# EVB_Gatedriver.net
KiCad netlist of a schematic drawn in Altium Designer
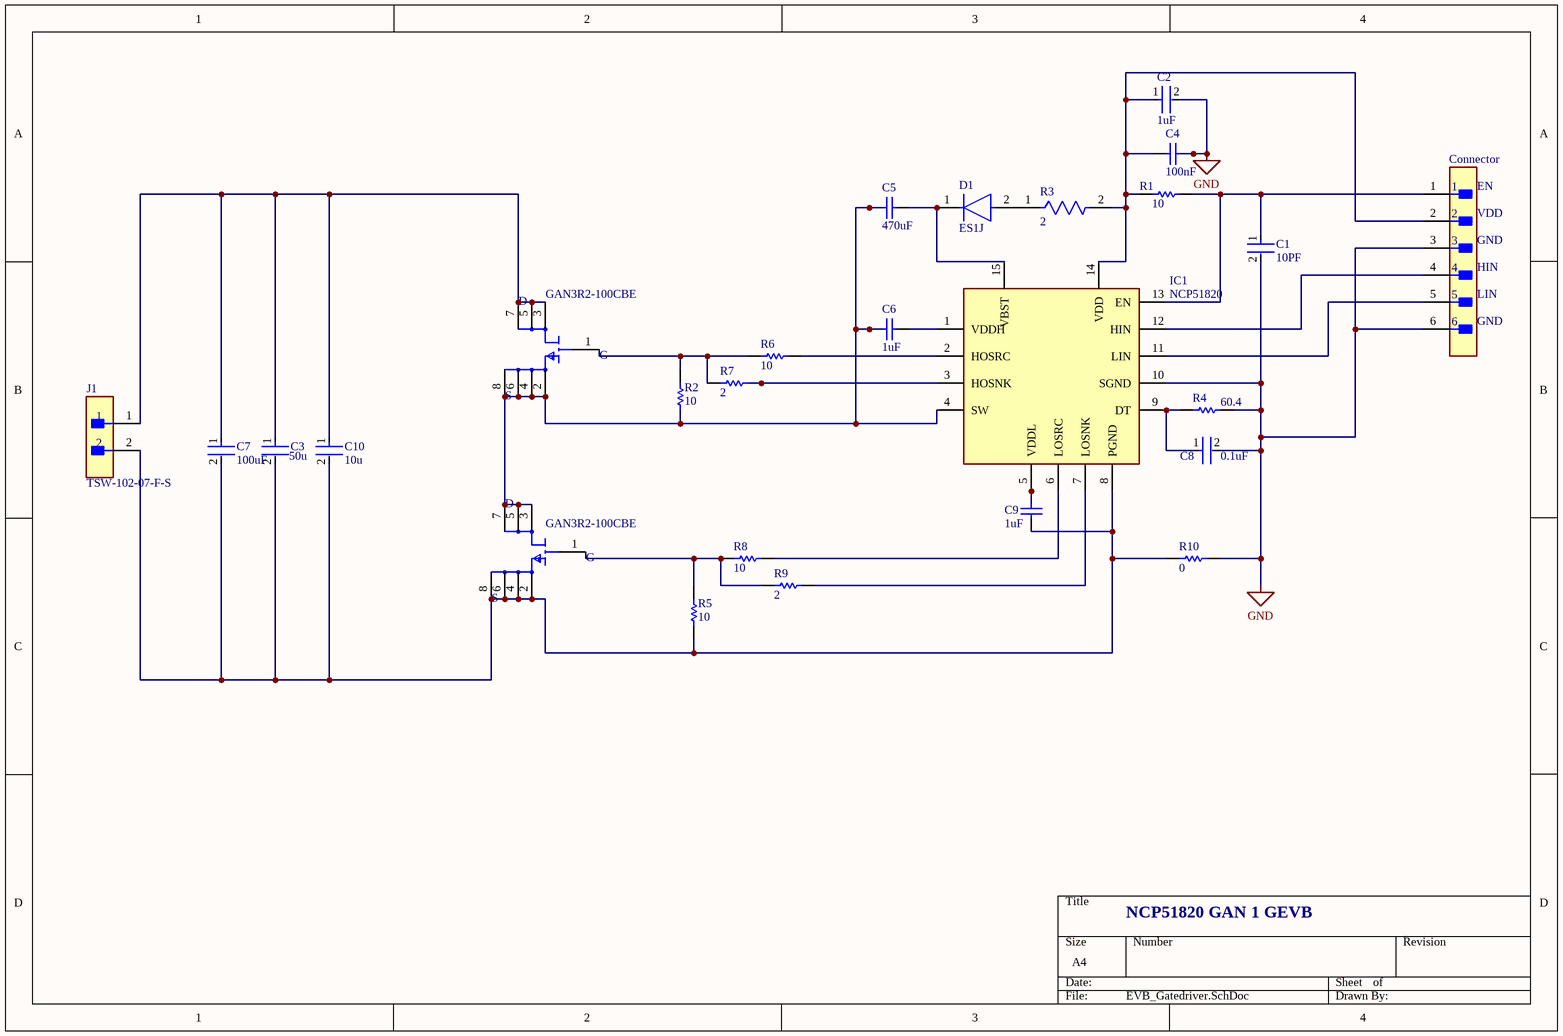
[diagram p0: EVB_Gatedriver.SchDoc]

(export (version "E")
  (design (tool "Eeschema 10.0.6"))
  (components
    (comp (ref "1")
      (value "GAN3R2-100CBE")
      (footprint "FP-WLCSP8-SOT8072-MFG")
      (libsource (lib "Alpha_library") (part "GAN3R2-100CBE_1"))
    )
    (comp (ref "2")
      (value "GAN3R2-100CBE")
      (footprint "FP-WLCSP8-SOT8072-MFG")
      (libsource (lib "Alpha_library") (part "GAN3R2-100CBE_1"))
    )
    (comp (ref "C1")
      (value "10PF")
      (footprint "FP-C1206C-EB-MFG")
      (description "CAP CER 10PF 50V C0G/NP0 1206")
      (fields
        (field (name "OCTOPART") "https://octopart.com/c1206c100j5gactu-kemet-87062")
        (field (name "MANUFACTURER PART NUMBER") "C1206C100J5GACTU")
      )
      (libsource (lib "Altium Content Vault") (part "b4654b650e69147ec39a6b967a45e02"))
    )
    (comp (ref "C2")
      (value "1uF")
      (footprint "FP-CC0805-0_85-MFG")
      (description "CC0805 1 uF X7R 10.00% 16 V")
      (fields (field (name "MANUFACTURER") "Yageo"))
      (libsource (lib "Altium Content Vault") (part "11868f565c42a9108669ba33697ecf6"))
    )
    (comp (ref "C3")
      (value "50u")
      (footprint "FP-CGA5L-0_3-0_1-IPC_B")
      (description "Cap Ceramic 100nF 450V X7T 10% Pad SMD 1206 +125°C Automotive T/R")
      (fields (field (name "TOLERANCE") "10%"))
      (libsource (lib "Altium Content Vault") (part "b4654b650e69147ec39a6b967a45e02"))
    )
    (comp (ref "C4")
      (value "100nF")
      (footprint "CAPC2013X145X48LL20T23")
      (fields (field (name "MANUFACTURER") "Vitramon") (field (name "PART NUMBER") "VJ0805Y104JXXAT"))
      (libsource (lib "Altium Content Vault") (part "CAP"))
    )
    (comp (ref "C5")
      (value "470uF")
      (footprint "CAPC2013X140X50ML20T25")
      (fields
        (field (name "MANUFACTURER") "AVX Interconnect / Elco")
        (field (name "PART NUMBER") "08053D474KAT2A")
      )
      (libsource (lib "Altium Content Vault") (part "CAP"))
    )
    (comp (ref "C6")
      (value "1uF")
      (footprint "CAPC2013X140X50NL20T25")
      (fields (field (name "MANUFACTURER") "Kemet") (field (name "PART NUMBER") "C0805C105K3PACTU"))
      (libsource (lib "Altium Content Vault") (part "CAP"))
    )
    (comp (ref "C7")
      (value "100uF")
      (footprint "FP-CGA5L-0_3-0_1-IPC_B")
      (description "Cap Ceramic 100nF 450V X7T 10% Pad SMD 1206 +125°C Automotive T/R")
      (fields (field (name "TOLERANCE") "10%"))
      (libsource (lib "Altium Content Vault") (part "b4654b650e69147ec39a6b967a45e02"))
    )
    (comp (ref "C8")
      (value "0.1uF")
      (footprint "FP-C1206C-EB-MFG")
      (description "CAP CER 0.1UF 25V 10% X7R 1206")
      (fields
        (field (name "MANUFACTURER") "KEMET")
        (field (name "OCTOPART") "https://octopart.com/c1206c104k3ractu-kemet-9144317")
      )
      (libsource (lib "Altium Content Vault") (part "b4654b650e69147ec39a6b967a45e02"))
    )
    (comp (ref "C9")
      (value "1uF")
      (footprint "CAPC2013X140X50NL20T25")
      (fields (field (name "MANUFACTURER") "Kemet") (field (name "PART NUMBER") "C0805C105K3PACTU"))
      (libsource (lib "Altium Content Vault") (part "CAP"))
    )
    (comp (ref "C10")
      (value "10u")
      (footprint "FP-CGA5L-0_3-0_1-IPC_B")
      (description "Cap Ceramic 100nF 450V X7T 10% Pad SMD 1206 +125°C Automotive T/R")
      (fields (field (name "TOLERANCE") "10%"))
      (libsource (lib "Altium Content Vault") (part "b4654b650e69147ec39a6b967a45e02"))
    )
    (comp (ref "Connector")
      (value "~")
      (footprint "FP-22-28-4060-MFG")
      (description "CONN HEADER VERT 6POS 2.54MM")
      (fields (field (name "MPN") "22-28-4060"))
      (libsource (lib "Altium Content Vault") (part "f2cb566baf1c37ab5a3b8e90bbeafd6"))
    )
    (comp (ref "D1")
      (value "ES1J")
      (footprint "FP-403AE-MFG")
      (description "DIODE GEN PURP 400V 1A SMA")
      (fields
        (field (name "OCTOPART") "https://octopart.com/es1g-on+semiconductor-84324858")
        (field (name "MANUFACTURER") "ON Semiconductor")
      )
      (libsource (lib "Altium Content Vault") (part "d7152d700b627762746794eb795d46e"))
    )
    (comp (ref "IC1")
      (value "NCP51820")
      (footprint "NCP51820")
      (description "Integrated Circuit")
      (libsource (lib "Alpha_library") (part "NCP51820"))
    )
    (comp (ref "J1")
      (value "TSW-102-07-F-S")
      (footprint "FP-TSW-102-07-F-S-MFG")
      (description "CONN HEADER VERT 2POS 2.54MM")
      (libsource (lib "Altium Content Vault") (part "3bc925449376181038e59eaffc5286c"))
    )
    (comp (ref "R1")
      (value "10")
      (footprint "RESC2013X60X35NL10T20")
      (description "Chip Resistor, 10 KOhm, +/- 1%, 0.125 W, -55 to 155 degC, 0805 (2012 Metric), RoHS, Tape and Reel")
      (fields (field (name "MANUFACTURER") "Yageo"))
      (libsource (lib "Altium Content Vault") (part "RES-2"))
    )
    (comp (ref "R2")
      (value "10")
      (footprint "RESC2013X60X35NL10T20")
      (description "Chip Resistor, 10 KOhm, +/- 1%, 0.125 W, -55 to 155 degC, 0805 (2012 Metric), RoHS, Tape and Reel")
      (fields (field (name "MANUFACTURER") "Yageo"))
      (libsource (lib "Altium Content Vault") (part "RES-2"))
    )
    (comp (ref "R3")
      (value "2")
      (footprint "FP-CRCW0805-e3-IPC_A")
      (description "RES Thick Film, 2Ω, 1%, 0.125W, 100ppm/°C, 0805")
      (fields (field (name "TOLERANCE") "1%"))
      (libsource (lib "Altium Content Vault") (part "1029c3af85768c4190bb7ad29bc67b5"))
    )
    (comp (ref "R4")
      (value "60.4")
      (footprint "RESC3116X65X40LL10T20")
      (fields (field (name "PART NUMBER") "RC1206FR-1360R4L") (field (name "MANUFACTURER") "Yageo"))
      (libsource (lib "Altium Content Vault") (part "RES"))
    )
    (comp (ref "R5")
      (value "10")
      (footprint "RESC2013X60X35NL10T20")
      (description "Chip Resistor, 10 KOhm, +/- 1%, 0.125 W, -55 to 155 degC, 0805 (2012 Metric), RoHS, Tape and Reel")
      (fields (field (name "MANUFACTURER") "Yageo"))
      (libsource (lib "Altium Content Vault") (part "RES-2"))
    )
    (comp (ref "R6")
      (value "10")
      (footprint "RESC2013X60X35LL10T20")
      (fields (field (name "PART NUMBER") "RC0805FR-1310RL") (field (name "MANUFACTURER") "Yageo"))
      (libsource (lib "Altium Content Vault") (part "RES"))
    )
    (comp (ref "R7")
      (value "2")
      (footprint "RESC2013X60X35LL10T20")
      (fields (field (name "PART NUMBER") "RC0805JR-072RL") (field (name "MANUFACTURER") "Yageo"))
      (libsource (lib "Altium Content Vault") (part "RES"))
    )
    (comp (ref "R8")
      (value "10")
      (footprint "RESC2013X60X35LL10T20")
      (fields (field (name "PART NUMBER") "RC0805FR-1310RL") (field (name "MANUFACTURER") "Yageo"))
      (libsource (lib "Altium Content Vault") (part "RES"))
    )
    (comp (ref "R9")
      (value "2")
      (footprint "RESC2013X60X35LL10T20")
      (fields (field (name "PART NUMBER") "RC0805JR-072RL") (field (name "MANUFACTURER") "Yageo"))
      (libsource (lib "Altium Content Vault") (part "RES"))
    )
    (comp (ref "R10")
      (value "0")
      (footprint "RESC1608X55X25ML10T15")
      (description "Chip Resistor, 0 Ohm, +/- 5%, 0.1 W, -55 to 155 degC, 0603 (1608 Metric), RoHS, Tape and Reel")
      (fields (field (name "TOLERANCE") "5%") (field (name "MANUFACTURER") "Yageo"))
      (libsource (lib "Altium Content Vault") (part "RES-2"))
    )
  )
  (nets
    (net (code "1") (name "GND") (class "Default")
      (node (ref "C1") (pin "2") (pinfunction "2_2") (pintype "passive"))
      (node (ref "C2") (pin "2") (pinfunction "2_2") (pintype "passive"))
      (node (ref "C4") (pin "2") (pinfunction "2_2") (pintype "passive"))
      (node (ref "C8") (pin "2") (pinfunction "2_2") (pintype "passive"))
      (node (ref "Connector") (pin "3") (pinfunction "3_3") (pintype "passive"))
      (node (ref "Connector") (pin "6") (pinfunction "6_6") (pintype "passive"))
      (node (ref "IC1") (pin "10") (pinfunction "SGND_10") (pintype "passive"))
      (node (ref "R10") (pin "2") (pinfunction "2_2") (pintype "passive"))
      (node (ref "R4") (pin "2") (pinfunction "2_2") (pintype "passive"))
    )
    (net (code "2") (name "Net-(1-D-Pad3)") (class "Default")
      (node (ref "1") (pin "3") (pinfunction "D_3") (pintype "passive"))
      (node (ref "1") (pin "5") (pinfunction "D_5") (pintype "passive"))
      (node (ref "1") (pin "7") (pinfunction "D_7") (pintype "passive"))
      (node (ref "C10") (pin "1") (pinfunction "1_1") (pintype "passive"))
      (node (ref "C3") (pin "1") (pinfunction "1_1") (pintype "passive"))
      (node (ref "C7") (pin "1") (pinfunction "1_1") (pintype "passive"))
      (node (ref "J1") (pin "1") (pinfunction "1_1") (pintype "passive"))
    )
    (net (code "3") (name "Net-(1-G)") (class "Default")
      (node (ref "1") (pin "1") (pinfunction "G_1") (pintype "passive"))
      (node (ref "R2") (pin "2") (pinfunction "2_2") (pintype "passive"))
      (node (ref "R6") (pin "1") (pinfunction "1_1") (pintype "passive"))
      (node (ref "R7") (pin "1") (pinfunction "1_1") (pintype "passive"))
    )
    (net (code "4") (name "Net-(2-G)") (class "Default")
      (node (ref "2") (pin "1") (pinfunction "G_1") (pintype "passive"))
      (node (ref "R5") (pin "2") (pinfunction "2_2") (pintype "passive"))
      (node (ref "R8") (pin "1") (pinfunction "1_1") (pintype "passive"))
      (node (ref "R9") (pin "1") (pinfunction "1_1") (pintype "passive"))
    )
    (net (code "5") (name "Net-(D1-A)") (class "Default")
      (node (ref "D1") (pin "2") (pinfunction "A_2") (pintype "passive"))
      (node (ref "R3") (pin "1") (pinfunction "1_1") (pintype "passive"))
    )
    (net (code "6") (name "Net-(D1-C)") (class "Default")
      (node (ref "C5") (pin "2") (pinfunction "2_2") (pintype "passive"))
      (node (ref "D1") (pin "1") (pinfunction "C_1") (pintype "passive"))
      (node (ref "IC1") (pin "15") (pinfunction "VBST_15") (pintype "passive"))
    )
    (net (code "7") (name "Net-(IC1-DT)") (class "Default")
      (node (ref "C8") (pin "1") (pinfunction "1_1") (pintype "passive"))
      (node (ref "IC1") (pin "9") (pinfunction "DT_9") (pintype "passive"))
      (node (ref "R4") (pin "1") (pinfunction "1_1") (pintype "passive"))
    )
    (net (code "8") (name "Net-(IC1-EN)") (class "Default")
      (node (ref "C1") (pin "1") (pinfunction "1_1") (pintype "passive"))
      (node (ref "Connector") (pin "1") (pinfunction "1_1") (pintype "passive"))
      (node (ref "IC1") (pin "13") (pinfunction "EN_13") (pintype "passive"))
      (node (ref "R1") (pin "1") (pinfunction "1_1") (pintype "passive"))
    )
    (net (code "9") (name "Net-(IC1-HIN)") (class "Default")
      (node (ref "Connector") (pin "4") (pinfunction "4_4") (pintype "passive"))
      (node (ref "IC1") (pin "12") (pinfunction "HIN_12") (pintype "passive"))
    )
    (net (code "10") (name "Net-(IC1-HOSNK)") (class "Default")
      (node (ref "IC1") (pin "3") (pinfunction "HOSNK_3") (pintype "passive"))
      (node (ref "R7") (pin "2") (pinfunction "2_2") (pintype "passive"))
    )
    (net (code "11") (name "Net-(IC1-HOSRC)") (class "Default")
      (node (ref "IC1") (pin "2") (pinfunction "HOSRC_2") (pintype "passive"))
      (node (ref "R6") (pin "2") (pinfunction "2_2") (pintype "passive"))
    )
    (net (code "12") (name "Net-(IC1-LIN)") (class "Default")
      (node (ref "Connector") (pin "5") (pinfunction "5_5") (pintype "passive"))
      (node (ref "IC1") (pin "11") (pinfunction "LIN_11") (pintype "passive"))
    )
    (net (code "13") (name "Net-(IC1-LOSNK)") (class "Default")
      (node (ref "IC1") (pin "7") (pinfunction "LOSNK_7") (pintype "passive"))
      (node (ref "R9") (pin "2") (pinfunction "2_2") (pintype "passive"))
    )
    (net (code "14") (name "Net-(IC1-LOSRC)") (class "Default")
      (node (ref "IC1") (pin "6") (pinfunction "LOSRC_6") (pintype "passive"))
      (node (ref "R8") (pin "2") (pinfunction "2_2") (pintype "passive"))
    )
    (net (code "15") (name "Net-(IC1-PGND)") (class "Default")
      (node (ref "2") (pin "2") (pinfunction "S_2") (pintype "passive"))
      (node (ref "2") (pin "4") (pinfunction "S_4") (pintype "passive"))
      (node (ref "2") (pin "6") (pinfunction "S_6") (pintype "passive"))
      (node (ref "2") (pin "8") (pinfunction "S_8") (pintype "passive"))
      (node (ref "C10") (pin "2") (pinfunction "2_2") (pintype "passive"))
      (node (ref "C3") (pin "2") (pinfunction "2_2") (pintype "passive"))
      (node (ref "C7") (pin "2") (pinfunction "2_2") (pintype "passive"))
      (node (ref "C9") (pin "1") (pinfunction "1_1") (pintype "passive"))
      (node (ref "IC1") (pin "8") (pinfunction "PGND_8") (pintype "passive"))
      (node (ref "J1") (pin "2") (pinfunction "2_2") (pintype "passive"))
      (node (ref "R10") (pin "1") (pinfunction "1_1") (pintype "passive"))
      (node (ref "R5") (pin "1") (pinfunction "1_1") (pintype "passive"))
    )
    (net (code "16") (name "Net-(IC1-SW)") (class "Default")
      (node (ref "1") (pin "2") (pinfunction "S_2") (pintype "passive"))
      (node (ref "1") (pin "4") (pinfunction "S_4") (pintype "passive"))
      (node (ref "1") (pin "6") (pinfunction "S_6") (pintype "passive"))
      (node (ref "1") (pin "8") (pinfunction "S_8") (pintype "passive"))
      (node (ref "2") (pin "3") (pinfunction "D_3") (pintype "passive"))
      (node (ref "2") (pin "5") (pinfunction "D_5") (pintype "passive"))
      (node (ref "2") (pin "7") (pinfunction "D_7") (pintype "passive"))
      (node (ref "C5") (pin "1") (pinfunction "1_1") (pintype "passive"))
      (node (ref "C6") (pin "1") (pinfunction "1_1") (pintype "passive"))
      (node (ref "IC1") (pin "4") (pinfunction "SW_4") (pintype "passive"))
      (node (ref "R2") (pin "1") (pinfunction "1_1") (pintype "passive"))
    )
    (net (code "17") (name "Net-(IC1-VDD)") (class "Default")
      (node (ref "C2") (pin "1") (pinfunction "1_1") (pintype "passive"))
      (node (ref "C4") (pin "1") (pinfunction "1_1") (pintype "passive"))
      (node (ref "Connector") (pin "2") (pinfunction "2_2") (pintype "passive"))
      (node (ref "IC1") (pin "14") (pinfunction "VDD_14") (pintype "passive"))
      (node (ref "R1") (pin "2") (pinfunction "2_2") (pintype "passive"))
      (node (ref "R3") (pin "2") (pinfunction "2_2") (pintype "passive"))
    )
    (net (code "18") (name "Net-(IC1-VDDH)") (class "Default")
      (node (ref "C6") (pin "2") (pinfunction "2_2") (pintype "passive"))
      (node (ref "IC1") (pin "1") (pinfunction "VDDH_1") (pintype "passive"))
    )
    (net (code "19") (name "Net-(IC1-VDDL)") (class "Default")
      (node (ref "C9") (pin "2") (pinfunction "2_2") (pintype "passive"))
      (node (ref "IC1") (pin "5") (pinfunction "VDDL_5") (pintype "passive"))
    )
  )
)
